# FlightComputer_RevA.net
KiCad netlist of a schematic drawn in EAGLE
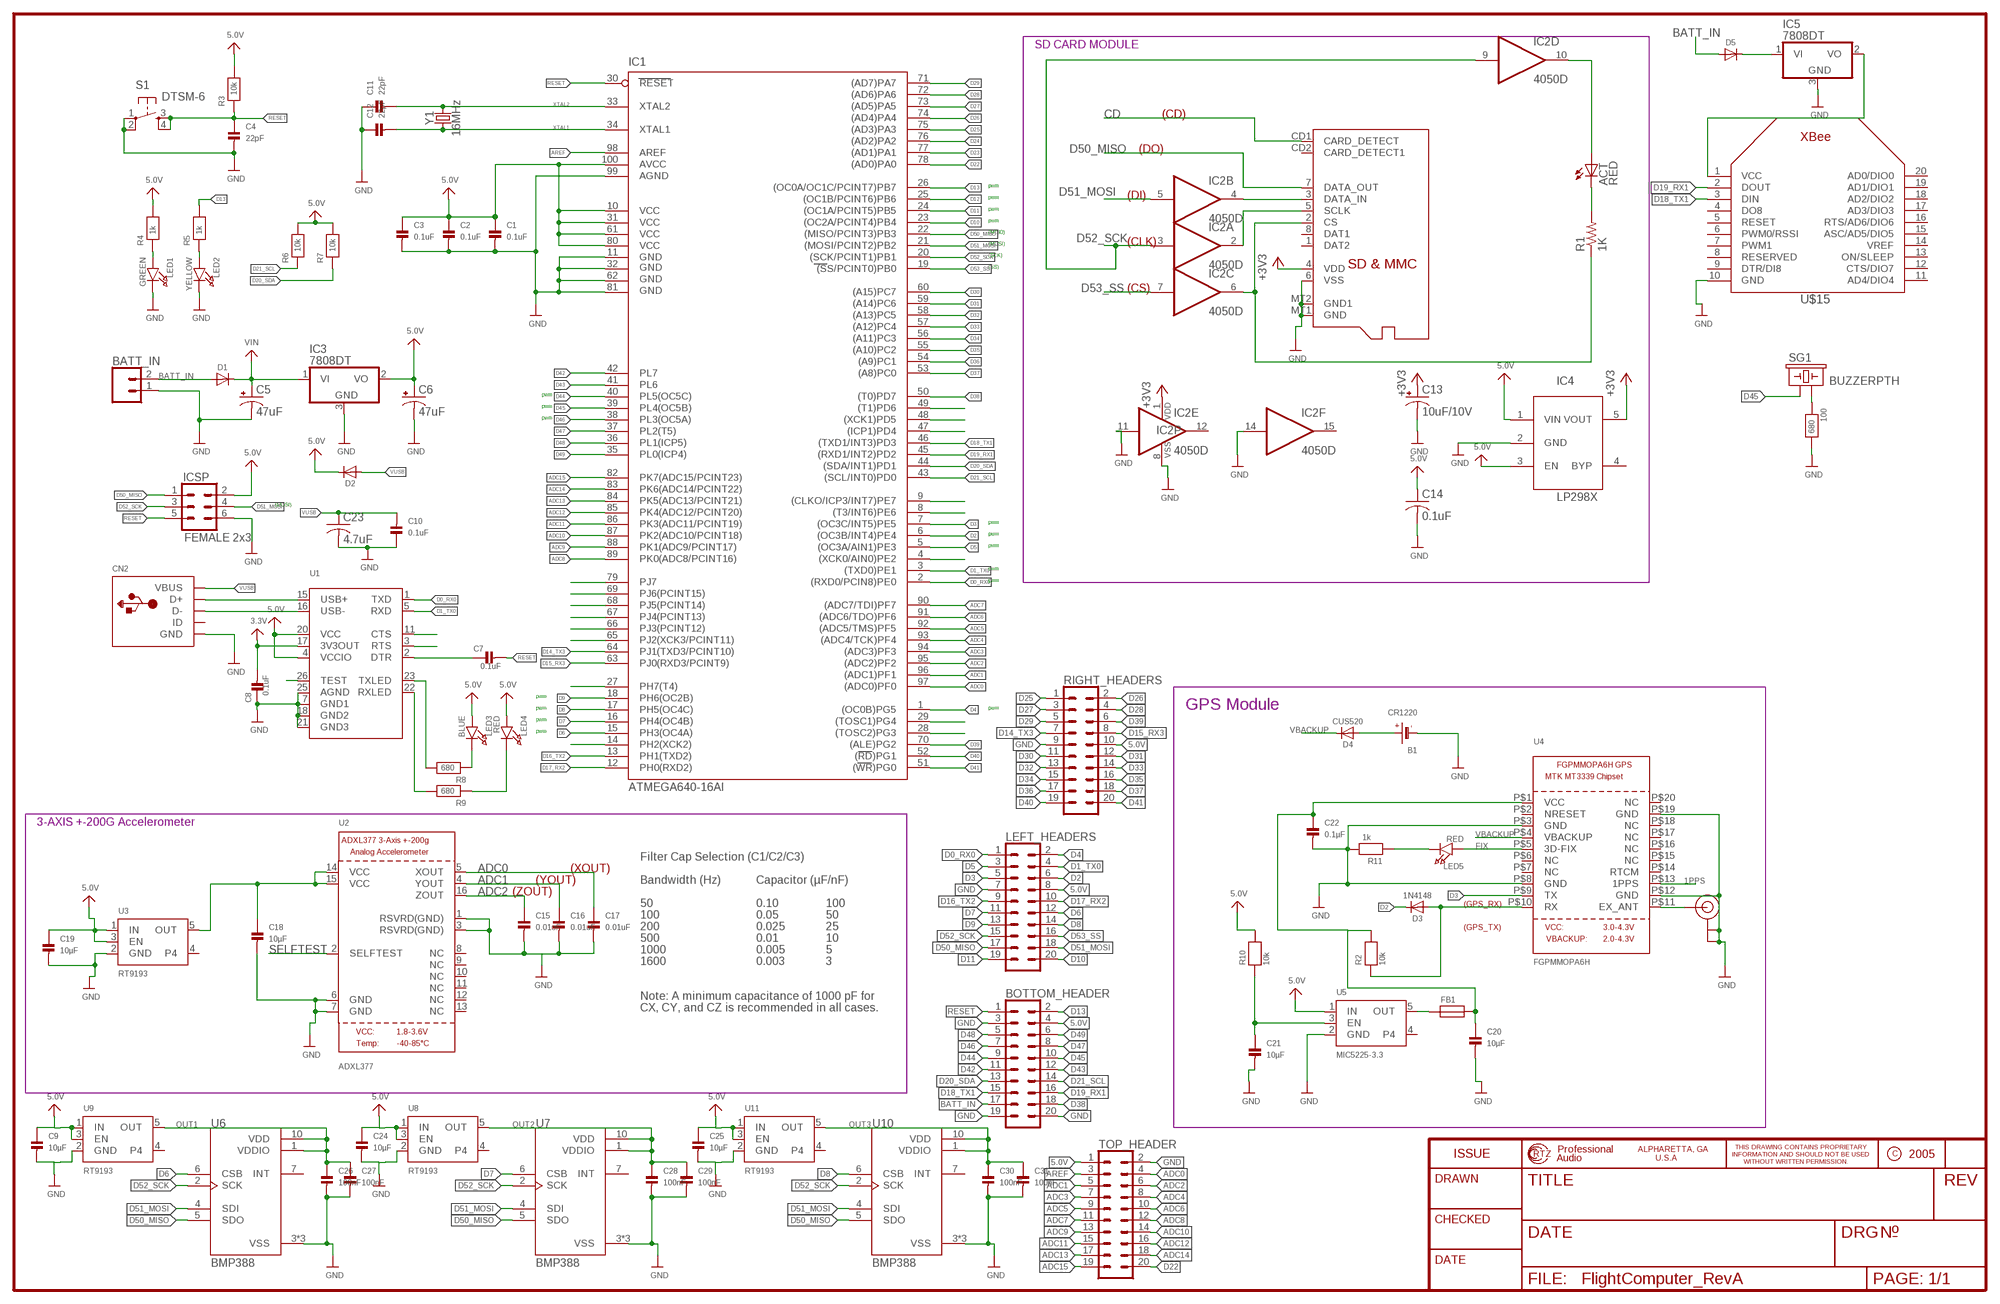
[diagram p0: schematic, sheet 1]

(export (version "E")
  (design (tool "Eeschema 10.0.6"))
  (components
    (comp (ref "100")
      (value "680")
      (footprint "eagle-import:0603")
      (libsource (lib "eagle-import") (part "RESISTOR0603"))
    )
    (comp (ref "ACT")
      (value "RED")
      (footprint "eagle-import:CHIP-LED0805")
      (libsource (lib "eagle-import") (part "LEDCHIP-LED0805"))
    )
    (comp (ref "B1")
      (value "CR1220")
      (footprint "eagle-import:CR1220")
      (libsource (lib "eagle-import") (part "BATTERYCR1220_SMT"))
    )
    (comp (ref "BATT_IN")
      (value "CONN_02")
      (footprint "eagle-import:1X02")
      (libsource (lib "eagle-import") (part "CONN_02"))
    )
    (comp (ref "BOTTOM_HEADER")
      (value "CONN_10X2")
      (footprint "eagle-import:2X10")
      (libsource (lib "eagle-import") (part "CONN_10X2"))
    )
    (comp (ref "C1")
      (value "0.1uF")
      (footprint "eagle-import:0603")
      (libsource (lib "eagle-import") (part "CAP_CERAMIC0603"))
    )
    (comp (ref "C2")
      (value "0.1uF")
      (footprint "eagle-import:0603")
      (libsource (lib "eagle-import") (part "CAP_CERAMIC0603"))
    )
    (comp (ref "C3")
      (value "0.1uF")
      (footprint "eagle-import:0603")
      (libsource (lib "eagle-import") (part "CAP_CERAMIC0603"))
    )
    (comp (ref "C4")
      (value "22pF")
      (footprint "eagle-import:0603")
      (libsource (lib "eagle-import") (part "CAP_CERAMIC0603"))
    )
    (comp (ref "C5")
      (value "47uF")
      (footprint "eagle-import:PANASONIC_D")
      (libsource (lib "eagle-import") (part "rcl_334_CPOL-USD"))
    )
    (comp (ref "C6")
      (value "47uF")
      (footprint "eagle-import:PANASONIC_D")
      (libsource (lib "eagle-import") (part "rcl_334_CPOL-USD"))
    )
    (comp (ref "C7")
      (value "0.1uF")
      (footprint "eagle-import:0603")
      (libsource (lib "eagle-import") (part "CAP_CERAMIC0603"))
    )
    (comp (ref "C8")
      (value "0.1uF")
      (footprint "eagle-import:0603")
      (libsource (lib "eagle-import") (part "CAP_CERAMIC0603"))
    )
    (comp (ref "C9")
      (value "10µF")
      (footprint "eagle-import:0603")
      (libsource (lib "eagle-import") (part "CAP_CERAMIC0603"))
    )
    (comp (ref "C10")
      (value "0.1uF")
      (footprint "eagle-import:0603")
      (libsource (lib "eagle-import") (part "CAP_CERAMIC0603"))
    )
    (comp (ref "C11")
      (value "22pF")
      (footprint "eagle-import:0603")
      (libsource (lib "eagle-import") (part "CAP_CERAMIC0603"))
    )
    (comp (ref "C12")
      (value "22pF")
      (footprint "eagle-import:0603")
      (libsource (lib "eagle-import") (part "CAP_CERAMIC0603"))
    )
    (comp (ref "C13")
      (value "10uF/10V")
      (footprint "eagle-import:A_3216-18R")
      (libsource (lib "eagle-import") (part "CPOL-USA/3216-18R"))
    )
    (comp (ref "C14")
      (value "0.1uF")
      (footprint "eagle-import:C0805K")
      (libsource (lib "eagle-import") (part "C-USC0805K"))
    )
    (comp (ref "C15")
      (value "0.01uF")
      (footprint "eagle-import:0603")
      (libsource (lib "eagle-import") (part "CAP_CERAMIC0603"))
    )
    (comp (ref "C16")
      (value "0.01uF")
      (footprint "eagle-import:0603")
      (libsource (lib "eagle-import") (part "CAP_CERAMIC0603"))
    )
    (comp (ref "C17")
      (value "0.01uF")
      (footprint "eagle-import:0603")
      (libsource (lib "eagle-import") (part "CAP_CERAMIC0603"))
    )
    (comp (ref "C18")
      (value "10µF")
      (footprint "eagle-import:0603")
      (libsource (lib "eagle-import") (part "CAP_CERAMIC0603"))
    )
    (comp (ref "C19")
      (value "10µF")
      (footprint "eagle-import:0603")
      (libsource (lib "eagle-import") (part "CAP_CERAMIC0603"))
    )
    (comp (ref "C20")
      (value "10µF")
      (footprint "eagle-import:0603")
      (libsource (lib "eagle-import") (part "CAP_CERAMIC0603"))
    )
    (comp (ref "C21")
      (value "10µF")
      (footprint "eagle-import:0603")
      (libsource (lib "eagle-import") (part "CAP_CERAMIC0603"))
    )
    (comp (ref "C22")
      (value "0.1µF")
      (footprint "eagle-import:0603")
      (libsource (lib "eagle-import") (part "CAP_CERAMIC0603"))
    )
    (comp (ref "C23")
      (value "4.7uF")
      (footprint "eagle-import:C0603")
      (libsource (lib "eagle-import") (part "C-USC0603"))
    )
    (comp (ref "C24")
      (value "10µF")
      (footprint "eagle-import:0603")
      (libsource (lib "eagle-import") (part "CAP_CERAMIC0603"))
    )
    (comp (ref "C25")
      (value "10µF")
      (footprint "eagle-import:0603")
      (libsource (lib "eagle-import") (part "CAP_CERAMIC0603"))
    )
    (comp (ref "C26")
      (value "100nF")
      (footprint "eagle-import:0603")
      (libsource (lib "eagle-import") (part "CAP_CERAMIC0603"))
    )
    (comp (ref "C27")
      (value "100nF")
      (footprint "eagle-import:0603")
      (libsource (lib "eagle-import") (part "CAP_CERAMIC0603"))
    )
    (comp (ref "C28")
      (value "100nF")
      (footprint "eagle-import:0603")
      (libsource (lib "eagle-import") (part "CAP_CERAMIC0603"))
    )
    (comp (ref "C29")
      (value "100nF")
      (footprint "eagle-import:0603")
      (libsource (lib "eagle-import") (part "CAP_CERAMIC0603"))
    )
    (comp (ref "C30")
      (value "100nF")
      (footprint "eagle-import:0603")
      (libsource (lib "eagle-import") (part "CAP_CERAMIC0603"))
    )
    (comp (ref "C31")
      (value "100nF")
      (footprint "eagle-import:0603")
      (libsource (lib "eagle-import") (part "CAP_CERAMIC0603"))
    )
    (comp (ref "CN2")
      (value "USBMINIB")
      (footprint "eagle-import:USB-MINIB")
      (libsource (lib "eagle-import") (part "USBMINIB"))
    )
    (comp (ref "D1")
      (value "DIODESOD-123")
      (footprint "eagle-import:SOD-123")
      (libsource (lib "eagle-import") (part "DIODESOD-123"))
    )
    (comp (ref "D2")
      (value "DIODESOD-123")
      (footprint "eagle-import:SOD-123")
      (libsource (lib "eagle-import") (part "DIODESOD-123"))
    )
    (comp (ref "D3")
      (value "1N4148")
      (footprint "eagle-import:SOD-323")
      (libsource (lib "eagle-import") (part "DIODESOD-323"))
    )
    (comp (ref "D4")
      (value "CUS520")
      (footprint "eagle-import:SOD-323")
      (libsource (lib "eagle-import") (part "DIODESOD-323"))
    )
    (comp (ref "D5")
      (value "DIODESOD-123")
      (footprint "eagle-import:SOD-123")
      (libsource (lib "eagle-import") (part "DIODESOD-123"))
    )
    (comp (ref "FB1")
      (value "FERRITE")
      (footprint "eagle-import:0603")
      (libsource (lib "eagle-import") (part "FERRITE"))
    )
    (comp (ref "IC1")
      (value "ATMEGA640-16AI")
      (footprint "eagle-import:TQFP100")
      (libsource (lib "eagle-import") (part "ATMEGAAI640-16"))
    )
    (comp (ref "IC2")
      (value "4050D")
      (footprint "eagle-import:SO16")
      (libsource (lib "eagle-import") (part "4050D"))
    )
    (comp (ref "IC3")
      (value "7808DT")
      (footprint "eagle-import:TO252")
      (libsource (lib "eagle-import") (part "78DT08"))
    )
    (comp (ref "IC4")
      (value "LP298XS")
      (footprint "eagle-import:SOT23-5L")
      (libsource (lib "eagle-import") (part "LP298XS"))
    )
    (comp (ref "IC5")
      (value "7808DT")
      (footprint "eagle-import:TO252")
      (libsource (lib "eagle-import") (part "78DT08"))
    )
    (comp (ref "ICSP")
      (value "FEMALE 2x3")
      (footprint "eagle-import:2X3")
      (libsource (lib "eagle-import") (part "CONN_03X2FEMALE"))
    )
    (comp (ref "LED1")
      (value "GREEN")
      (footprint "eagle-import:CHIPLED_0603")
      (libsource (lib "eagle-import") (part "LED0603"))
    )
    (comp (ref "LED2")
      (value "YELLOW")
      (footprint "eagle-import:CHIPLED_0603")
      (libsource (lib "eagle-import") (part "LED0603"))
    )
    (comp (ref "LED3")
      (value "BLUE")
      (footprint "eagle-import:CHIPLED_0603")
      (libsource (lib "eagle-import") (part "LED0603"))
    )
    (comp (ref "LED4")
      (value "RED")
      (footprint "eagle-import:CHIPLED_0603")
      (libsource (lib "eagle-import") (part "LED0603"))
    )
    (comp (ref "LED5")
      (value "RED")
      (footprint "eagle-import:CHIPLED_0805")
      (libsource (lib "eagle-import") (part "LED0805"))
    )
    (comp (ref "LEFT_HEADERS")
      (value "CONN_10X2")
      (footprint "eagle-import:2X10")
      (libsource (lib "eagle-import") (part "CONN_10X2"))
    )
    (comp (ref "R1")
      (value "1K")
      (footprint "eagle-import:R0805")
      (libsource (lib "eagle-import") (part "R-US_R0805"))
    )
    (comp (ref "R2")
      (value "10k")
      (footprint "eagle-import:0603")
      (libsource (lib "eagle-import") (part "RESISTOR0603"))
    )
    (comp (ref "R3")
      (value "10k")
      (footprint "eagle-import:0603")
      (libsource (lib "eagle-import") (part "RESISTOR0603"))
    )
    (comp (ref "R4")
      (value "1k")
      (footprint "eagle-import:0603")
      (libsource (lib "eagle-import") (part "RESISTOR0603"))
    )
    (comp (ref "R5")
      (value "1k")
      (footprint "eagle-import:0603")
      (libsource (lib "eagle-import") (part "RESISTOR0603"))
    )
    (comp (ref "R6")
      (value "10k")
      (footprint "eagle-import:0603")
      (libsource (lib "eagle-import") (part "RESISTOR0603"))
    )
    (comp (ref "R7")
      (value "10k")
      (footprint "eagle-import:0603")
      (libsource (lib "eagle-import") (part "RESISTOR0603"))
    )
    (comp (ref "R8")
      (value "680")
      (footprint "eagle-import:0603")
      (libsource (lib "eagle-import") (part "RESISTOR0603"))
    )
    (comp (ref "R9")
      (value "680")
      (footprint "eagle-import:0603")
      (libsource (lib "eagle-import") (part "RESISTOR0603"))
    )
    (comp (ref "R10")
      (value "10k")
      (footprint "eagle-import:0603")
      (libsource (lib "eagle-import") (part "RESISTOR0603"))
    )
    (comp (ref "R11")
      (value "1k")
      (footprint "eagle-import:0603")
      (libsource (lib "eagle-import") (part "RESISTOR0603"))
    )
    (comp (ref "RIGHT_HEADERS")
      (value "CONN_10X2")
      (footprint "eagle-import:2X10")
      (libsource (lib "eagle-import") (part "CONN_10X2"))
    )
    (comp (ref "S1")
      (value "DTSM-6")
      (footprint "eagle-import:DTSM-6")
      (libsource (lib "eagle-import") (part "DTSM-6"))
    )
    (comp (ref "SG1")
      (value "BUZZERPTH")
      (footprint "eagle-import:BUZZER-12MM")
      (libsource (lib "eagle-import") (part "BUZZERPTH"))
    )
    (comp (ref "TOP_HEADER")
      (value "CONN_10X2")
      (footprint "eagle-import:2X10")
      (libsource (lib "eagle-import") (part "CONN_10X2"))
    )
    (comp (ref "U$15")
      (value "XBEE")
      (footprint "eagle-import:XBEE")
      (libsource (lib "eagle-import") (part "XBEE"))
    )
    (comp (ref "U$55")
      (value "U.FL")
      (footprint "eagle-import:U.FL")
      (libsource (lib "eagle-import") (part "U.FL"))
    )
    (comp (ref "U1")
      (value "FT232RLSSOP28")
      (footprint "eagle-import:SSOP28DB")
      (libsource (lib "eagle-import") (part "FT232RLSSOP28"))
    )
    (comp (ref "U2")
      (value "ADXL377")
      (footprint "eagle-import:LFCSP16_LQ")
      (libsource (lib "eagle-import") (part "ACCEL_ADXL377"))
    )
    (comp (ref "U3")
      (value "RT9193")
      (footprint "eagle-import:SOT23-5")
      (libsource (lib "eagle-import") (part "VREG_SOT23-5"))
    )
    (comp (ref "U4")
      (value "FGPMMOPA6H")
      (footprint "eagle-import:FGPMMOPA6H")
      (libsource (lib "eagle-import") (part "GPS_FGPMMOPA6H"))
    )
    (comp (ref "U5")
      (value "MIC5225-3.3")
      (footprint "eagle-import:SOT23-5")
      (libsource (lib "eagle-import") (part "VREG_SOT23-5"))
    )
    (comp (ref "U6")
      (value "BMP388")
      (footprint "eagle-import:PQFN50P200X200X80-10N")
      (fields (field (name "MF") "Bosch Sensortec"))
      (libsource (lib "eagle-import") (part "BMP388"))
    )
    (comp (ref "U7")
      (value "BMP388")
      (footprint "eagle-import:PQFN50P200X200X80-10N")
      (fields (field (name "MF") "Bosch Sensortec"))
      (libsource (lib "eagle-import") (part "BMP388"))
    )
    (comp (ref "U8")
      (value "RT9193")
      (footprint "eagle-import:SOT23-5")
      (libsource (lib "eagle-import") (part "VREG_SOT23-5"))
    )
    (comp (ref "U9")
      (value "RT9193")
      (footprint "eagle-import:SOT23-5")
      (libsource (lib "eagle-import") (part "VREG_SOT23-5"))
    )
    (comp (ref "U10")
      (value "BMP388")
      (footprint "eagle-import:PQFN50P200X200X80-10N")
      (fields (field (name "MF") "Bosch Sensortec"))
      (libsource (lib "eagle-import") (part "BMP388"))
    )
    (comp (ref "U11")
      (value "RT9193")
      (footprint "eagle-import:SOT23-5")
      (libsource (lib "eagle-import") (part "VREG_SOT23-5"))
    )
    (comp (ref "X1")
      (value "MICROSD")
      (footprint "eagle-import:MICROSD")
      (libsource (lib "eagle-import") (part "MICROSD"))
    )
    (comp (ref "Y1")
      (value "16MHz")
      (footprint "eagle-import:HC49US")
      (libsource (lib "eagle-import") (part "CRYSTAL-16MHZPTH-HC49US"))
    )
  )
  (nets
    (net (code "1") (name "+3V3") (class "Default")
      (node (ref "C13") (pin "+") (pinfunction "+_+") (pintype "passive"))
      (node (ref "IC2") (pin "1") (pinfunction "VDD_1") (pintype "power_in"))
      (node (ref "IC4") (pin "5") (pinfunction "VOUT_5") (pintype "bidirectional"))
      (node (ref "X1") (pin "4") (pinfunction "VDD_4") (pintype "power_in"))
    )
    (net (code "2") (name "/1PPS") (class "Default")
      (node (ref "U4") (pin "P$13") (pinfunction "1PPS_P$13") (pintype "bidirectional"))
    )
    (net (code "3") (name "/CD") (class "Default")
      (node (ref "X1") (pin "CD1") (pinfunction "CARD_DETECT_CD1") (pintype "passive"))
    )
    (net (code "4") (name "/FIX") (class "Default")
      (node (ref "LED5") (pin "A") (pinfunction "A_A") (pintype "passive"))
      (node (ref "U4") (pin "P$5") (pinfunction "3D-FIX_P$5") (pintype "bidirectional"))
    )
    (net (code "5") (name "/OUT1") (class "Default")
      (node (ref "C26") (pin "1") (pinfunction "P$1_1") (pintype "passive"))
      (node (ref "C27") (pin "1") (pinfunction "P$1_1") (pintype "passive"))
      (node (ref "U6") (pin "1") (pinfunction "VDDIO_1") (pintype "power_in"))
      (node (ref "U6") (pin "10") (pinfunction "VDD_10") (pintype "power_in"))
      (node (ref "U9") (pin "5") (pinfunction "OUT_5") (pintype "power_in"))
    )
    (net (code "6") (name "/OUT2") (class "Default")
      (node (ref "C28") (pin "1") (pinfunction "P$1_1") (pintype "passive"))
      (node (ref "C29") (pin "1") (pinfunction "P$1_1") (pintype "passive"))
      (node (ref "U7") (pin "1") (pinfunction "VDDIO_1") (pintype "power_in"))
      (node (ref "U7") (pin "10") (pinfunction "VDD_10") (pintype "power_in"))
      (node (ref "U8") (pin "5") (pinfunction "OUT_5") (pintype "power_in"))
    )
    (net (code "7") (name "/OUT3") (class "Default")
      (node (ref "C30") (pin "1") (pinfunction "P$1_1") (pintype "passive"))
      (node (ref "C31") (pin "1") (pinfunction "P$1_1") (pintype "passive"))
      (node (ref "U10") (pin "1") (pinfunction "VDDIO_1") (pintype "power_in"))
      (node (ref "U10") (pin "10") (pinfunction "VDD_10") (pintype "power_in"))
      (node (ref "U11") (pin "5") (pinfunction "OUT_5") (pintype "power_in"))
    )
    (net (code "8") (name "/SELFTEST") (class "Default")
      (node (ref "U2") (pin "2") (pinfunction "SELFTEST_2") (pintype "bidirectional"))
    )
    (net (code "9") (name "/VBACKUP") (class "Default")
      (node (ref "D4") (pin "C") (pinfunction "C_C") (pintype "passive"))
      (node (ref "U4") (pin "P$4") (pinfunction "VBACKUP_P$4") (pintype "bidirectional"))
    )
    (net (code "10") (name "/XTAL1") (class "Default")
      (node (ref "C12") (pin "2") (pinfunction "P$2_2") (pintype "passive"))
      (node (ref "IC1") (pin "34") (pinfunction "XTAL1_34") (pintype "input"))
      (node (ref "Y1") (pin "1") (pinfunction "1_1") (pintype "passive"))
    )
    (net (code "11") (name "/XTAL2") (class "Default")
      (node (ref "C11") (pin "2") (pinfunction "P$2_2") (pintype "passive"))
      (node (ref "IC1") (pin "33") (pinfunction "XTAL2_33") (pintype "output"))
      (node (ref "Y1") (pin "2") (pinfunction "2_2") (pintype "passive"))
    )
    (net (code "12") (name "3.3V") (class "Default")
      (node (ref "C8") (pin "2") (pinfunction "P$2_2") (pintype "passive"))
      (node (ref "U1") (pin "17") (pinfunction "3V3OUT_17") (pintype "power_in"))
    )
    (net (code "13") (name "5.0V") (class "Default")
      (node (ref "BOTTOM_HEADER") (pin "4") (pinfunction "4_4") (pintype "passive"))
      (node (ref "C1") (pin "1") (pinfunction "P$1_1") (pintype "passive"))
      (node (ref "C14") (pin "1") (pinfunction "1_1") (pintype "passive"))
      (node (ref "C19") (pin "1") (pinfunction "P$1_1") (pintype "passive"))
      (node (ref "C2") (pin "1") (pinfunction "P$1_1") (pintype "passive"))
      (node (ref "C24") (pin "1") (pinfunction "P$1_1") (pintype "passive"))
      (node (ref "C25") (pin "1") (pinfunction "P$1_1") (pintype "passive"))
      (node (ref "C3") (pin "1") (pinfunction "P$1_1") (pintype "passive"))
      (node (ref "C6") (pin "+") (pinfunction "+_+") (pintype "passive"))
      (node (ref "C9") (pin "1") (pinfunction "P$1_1") (pintype "passive"))
      (node (ref "D2") (pin "C") (pinfunction "C_C") (pintype "passive"))
      (node (ref "IC1") (pin "10") (pinfunction "VCC_10") (pintype "power_in"))
      (node (ref "IC1") (pin "100") (pinfunction "AVCC_100") (pintype "power_in"))
      (node (ref "IC1") (pin "31") (pinfunction "VCC1_31") (pintype "power_in"))
      (node (ref "IC1") (pin "61") (pinfunction "VCC2_61") (pintype "power_in"))
      (node (ref "IC1") (pin "80") (pinfunction "VCC3_80") (pintype "power_in"))
      (node (ref "IC3") (pin "2") (pinfunction "VO_2") (pintype "passive"))
      (node (ref "IC4") (pin "1") (pinfunction "VIN_1") (pintype "bidirectional"))
      (node (ref "IC4") (pin "3") (pinfunction "EN_3") (pintype "bidirectional"))
      (node (ref "ICSP") (pin "2") (pinfunction "2_2") (pintype "bidirectional"))
      (node (ref "LED3") (pin "A") (pinfunction "A_A") (pintype "passive"))
      (node (ref "LED4") (pin "A") (pinfunction "A_A") (pintype "passive"))
      (node (ref "LEFT_HEADERS") (pin "8") (pinfunction "8_8") (pintype "passive"))
      (node (ref "R10") (pin "2") (pinfunction "2_2") (pintype "passive"))
      (node (ref "R3") (pin "2") (pinfunction "2_2") (pintype "passive"))
      (node (ref "R4") (pin "2") (pinfunction "2_2") (pintype "passive"))
      (node (ref "R6") (pin "2") (pinfunction "2_2") (pintype "passive"))
      (node (ref "R7") (pin "2") (pinfunction "2_2") (pintype "passive"))
      (node (ref "RIGHT_HEADERS") (pin "10") (pinfunction "10_10") (pintype "passive"))
      (node (ref "TOP_HEADER") (pin "1") (pinfunction "1_1") (pintype "passive"))
      (node (ref "U1") (pin "20") (pinfunction "VCC_20") (pintype "power_in"))
      (node (ref "U1") (pin "4") (pinfunction "VCCIO_4") (pintype "power_in"))
      (node (ref "U11") (pin "1") (pinfunction "IN_1") (pintype "power_in"))
      (node (ref "U11") (pin "3") (pinfunction "EN_3") (pintype "input"))
      (node (ref "U3") (pin "1") (pinfunction "IN_1") (pintype "power_in"))
      (node (ref "U3") (pin "3") (pinfunction "EN_3") (pintype "input"))
      (node (ref "U5") (pin "1") (pinfunction "IN_1") (pintype "power_in"))
      (node (ref "U8") (pin "1") (pinfunction "IN_1") (pintype "power_in"))
      (node (ref "U8") (pin "3") (pinfunction "EN_3") (pintype "input"))
      (node (ref "U9") (pin "1") (pinfunction "IN_1") (pintype "power_in"))
      (node (ref "U9") (pin "3") (pinfunction "EN_3") (pintype "input"))
    )
    (net (code "14") (name "ADC0") (class "Default")
      (node (ref "C17") (pin "1") (pinfunction "P$1_1") (pintype "passive"))
      (node (ref "IC1") (pin "97") (pinfunction "(ADC0)PF0_97") (pintype "bidirectional"))
      (node (ref "TOP_HEADER") (pin "4") (pinfunction "4_4") (pintype "passive"))
      (node (ref "U2") (pin "5") (pinfunction "XOUT_5") (pintype "output"))
    )
    (net (code "15") (name "ADC1") (class "Default")
      (node (ref "C16") (pin "1") (pinfunction "P$1_1") (pintype "passive"))
      (node (ref "IC1") (pin "96") (pinfunction "(ADC1)PF1_96") (pintype "bidirectional"))
      (node (ref "TOP_HEADER") (pin "5") (pinfunction "5_5") (pintype "passive"))
      (node (ref "U2") (pin "4") (pinfunction "YOUT_4") (pintype "output"))
    )
    (net (code "16") (name "ADC2") (class "Default")
      (node (ref "C15") (pin "1") (pinfunction "P$1_1") (pintype "passive"))
      (node (ref "IC1") (pin "95") (pinfunction "(ADC2)PF2_95") (pintype "bidirectional"))
      (node (ref "TOP_HEADER") (pin "6") (pinfunction "6_6") (pintype "passive"))
      (node (ref "U2") (pin "16") (pinfunction "ZOUT_16") (pintype "output"))
    )
    (net (code "17") (name "ADC3") (class "Default")
      (node (ref "IC1") (pin "94") (pinfunction "(ADC3)PF3_94") (pintype "bidirectional"))
      (node (ref "TOP_HEADER") (pin "7") (pinfunction "7_7") (pintype "passive"))
    )
    (net (code "18") (name "ADC4") (class "Default")
      (node (ref "IC1") (pin "93") (pinfunction "(ADC4/TCK)PF4_93") (pintype "bidirectional"))
      (node (ref "TOP_HEADER") (pin "8") (pinfunction "8_8") (pintype "passive"))
    )
    (net (code "19") (name "ADC5") (class "Default")
      (node (ref "IC1") (pin "92") (pinfunction "(ADC5/TMS)PF5_92") (pintype "bidirectional"))
      (node (ref "TOP_HEADER") (pin "9") (pinfunction "9_9") (pintype "passive"))
    )
    (net (code "20") (name "ADC6") (class "Default")
      (node (ref "IC1") (pin "91") (pinfunction "(ADC6/TDO)PF6_91") (pintype "bidirectional"))
      (node (ref "TOP_HEADER") (pin "10") (pinfunction "10_10") (pintype "passive"))
    )
    (net (code "21") (name "ADC7") (class "Default")
      (node (ref "IC1") (pin "90") (pinfunction "(ADC7/TDI)PF7_90") (pintype "bidirectional"))
      (node (ref "TOP_HEADER") (pin "11") (pinfunction "11_11") (pintype "passive"))
    )
    (net (code "22") (name "ADC8") (class "Default")
      (node (ref "IC1") (pin "89") (pinfunction "PK0(ADC8/PCINT16)_89") (pintype "bidirectional"))
      (node (ref "TOP_HEADER") (pin "12") (pinfunction "12_12") (pintype "passive"))
    )
    (net (code "23") (name "ADC9") (class "Default")
      (node (ref "IC1") (pin "88") (pinfunction "PK1(ADC9/PCINT17)_88") (pintype "bidirectional"))
      (node (ref "TOP_HEADER") (pin "13") (pinfunction "13_13") (pintype "passive"))
    )
    (net (code "24") (name "ADC10") (class "Default")
      (node (ref "IC1") (pin "87") (pinfunction "PK2(ADC10/PCINT18)_87") (pintype "bidirectional"))
      (node (ref "TOP_HEADER") (pin "14") (pinfunction "14_14") (pintype "passive"))
    )
    (net (code "25") (name "ADC11") (class "Default")
      (node (ref "IC1") (pin "86") (pinfunction "PK3(ADC11/PCINT19)_86") (pintype "bidirectional"))
      (node (ref "TOP_HEADER") (pin "15") (pinfunction "15_15") (pintype "passive"))
    )
    (net (code "26") (name "ADC12") (class "Default")
      (node (ref "IC1") (pin "85") (pinfunction "PK4(ADC12/PCINT20)_85") (pintype "bidirectional"))
      (node (ref "TOP_HEADER") (pin "16") (pinfunction "16_16") (pintype "passive"))
    )
    (net (code "27") (name "ADC13") (class "Default")
      (node (ref "IC1") (pin "84") (pinfunction "PK5(ADC13/PCINT21)_84") (pintype "bidirectional"))
      (node (ref "TOP_HEADER") (pin "17") (pinfunction "17_17") (pintype "passive"))
    )
    (net (code "28") (name "ADC14") (class "Default")
      (node (ref "IC1") (pin "83") (pinfunction "PK6(ADC14/PCINT22)_83") (pintype "bidirectional"))
      (node (ref "TOP_HEADER") (pin "18") (pinfunction "18_18") (pintype "passive"))
    )
    (net (code "29") (name "ADC15") (class "Default")
      (node (ref "IC1") (pin "82") (pinfunction "PK7(ADC15/PCINT23)_82") (pintype "bidirectional"))
      (node (ref "TOP_HEADER") (pin "19") (pinfunction "19_19") (pintype "passive"))
    )
    (net (code "30") (name "AREF") (class "Default")
      (node (ref "IC1") (pin "98") (pinfunction "AREF_98") (pintype "bidirectional"))
      (node (ref "TOP_HEADER") (pin "3") (pinfunction "3_3") (pintype "passive"))
    )
    (net (code "31") (name "BATT_IN") (class "Default")
      (node (ref "BATT_IN") (pin "2") (pinfunction "2_2") (pintype "passive"))
      (node (ref "BOTTOM_HEADER") (pin "17") (pinfunction "17_17") (pintype "passive"))
      (node (ref "D1") (pin "A") (pinfunction "A_A") (pintype "passive"))
      (node (ref "D5") (pin "A") (pinfunction "A_A") (pintype "passive"))
    )
    (net (code "32") (name "D0_RX0") (class "Default")
      (node (ref "IC1") (pin "2") (pinfunction "(RXD0/PCIN8)PE0_2") (pintype "bidirectional"))
      (node (ref "LEFT_HEADERS") (pin "1") (pinfunction "1_1") (pintype "passive"))
      (node (ref "U1") (pin "1") (pinfunction "TXD_1") (pintype "output"))
    )
    (net (code "33") (name "D1_TX0") (class "Default")
      (node (ref "IC1") (pin "3") (pinfunction "(TXD0)PE1_3") (pintype "bidirectional"))
      (node (ref "LEFT_HEADERS") (pin "4") (pinfunction "4_4") (pintype "passive"))
      (node (ref "U1") (pin "5") (pinfunction "RXD_5") (pintype "input"))
    )
    (net (code "34") (name "D2") (class "Default")
      (node (ref "D3") (pin "C") (pinfunction "C_C") (pintype "passive"))
      (node (ref "IC1") (pin "6") (pinfunction "(OC3B/INT4)PE4_6") (pintype "bidirectional"))
      (node (ref "LEFT_HEADERS") (pin "6") (pinfunction "6_6") (pintype "passive"))
    )
    (net (code "35") (name "D3") (class "Default")
      (node (ref "IC1") (pin "7") (pinfunction "(OC3C/INT5)PE5_7") (pintype "bidirectional"))
      (node (ref "LEFT_HEADERS") (pin "5") (pinfunction "5_5") (pintype "passive"))
      (node (ref "U4") (pin "P$9") (pinfunction "TX_P$9") (pintype "bidirectional"))
    )
    (net (code "36") (name "D4") (class "Default")
      (node (ref "IC1") (pin "1") (pinfunction "(OC0B)PG5_1") (pintype "bidirectional"))
      (node (ref "LEFT_HEADERS") (pin "2") (pinfunction "2_2") (pintype "passive"))
    )
    (net (code "37") (name "D5") (class "Default")
      (node (ref "IC1") (pin "5") (pinfunction "(OC3A/AIN1)PE3_5") (pintype "bidirectional"))
      (node (ref "LEFT_HEADERS") (pin "3") (pinfunction "3_3") (pintype "passive"))
    )
    (net (code "38") (name "D6") (class "Default")
      (node (ref "IC1") (pin "15") (pinfunction "PH3(OC4A)_15") (pintype "bidirectional"))
      (node (ref "LEFT_HEADERS") (pin "12") (pinfunction "12_12") (pintype "passive"))
      (node (ref "U6") (pin "6") (pinfunction "CSB_6") (pintype "input"))
    )
    (net (code "39") (name "D7") (class "Default")
      (node (ref "IC1") (pin "16") (pinfunction "PH4(OC4B)_16") (pintype "bidirectional"))
      (node (ref "LEFT_HEADERS") (pin "11") (pinfunction "11_11") (pintype "passive"))
      (node (ref "U7") (pin "6") (pinfunction "CSB_6") (pintype "input"))
    )
    (net (code "40") (name "D8") (class "Default")
      (node (ref "IC1") (pin "17") (pinfunction "PH5(OC4C)_17") (pintype "bidirectional"))
      (node (ref "LEFT_HEADERS") (pin "14") (pinfunction "14_14") (pintype "passive"))
      (node (ref "U10") (pin "6") (pinfunction "CSB_6") (pintype "input"))
    )
    (net (code "41") (name "D9") (class "Default")
      (node (ref "IC1") (pin "18") (pinfunction "PH6(OC2B)_18") (pintype "bidirectional"))
      (node (ref "LEFT_HEADERS") (pin "13") (pinfunction "13_13") (pintype "passive"))
    )
    (net (code "42") (name "D10") (class "Default")
      (node (ref "IC1") (pin "23") (pinfunction "(OC2A/PCINT4)PB4_23") (pintype "bidirectional"))
      (node (ref "LEFT_HEADERS") (pin "20") (pinfunction "20_20") (pintype "passive"))
    )
    (net (code "43") (name "D11") (class "Default")
      (node (ref "IC1") (pin "24") (pinfunction "(OC1A/PCINT5)PB5_24") (pintype "bidirectional"))
      (node (ref "LEFT_HEADERS") (pin "19") (pinfunction "19_19") (pintype "passive"))
    )
    (net (code "44") (name "D12") (class "Default")
      (node (ref "IC1") (pin "25") (pinfunction "(OC1B/PCINT6)PB6_25") (pintype "bidirectional"))
    )
    (net (code "45") (name "D13") (class "Default")
      (node (ref "BOTTOM_HEADER") (pin "2") (pinfunction "2_2") (pintype "passive"))
      (node (ref "IC1") (pin "26") (pinfunction "(OC0A/OC1C/PCINT7)PB7_26") (pintype "bidirectional"))
      (node (ref "R5") (pin "2") (pinfunction "2_2") (pintype "passive"))
    )
    (net (code "46") (name "D14_TX3") (class "Default")
      (node (ref "IC1") (pin "64") (pinfunction "PJ1(TXD3/PCINT10)_64") (pintype "bidirectional"))
      (node (ref "RIGHT_HEADERS") (pin "7") (pinfunction "7_7") (pintype "passive"))
    )
    (net (code "47") (name "D15_RX3") (class "Default")
      (node (ref "IC1") (pin "63") (pinfunction "PJ0(RXD3/PCINT9)_63") (pintype "bidirectional"))
      (node (ref "RIGHT_HEADERS") (pin "8") (pinfunction "8_8") (pintype "passive"))
    )
    (net (code "48") (name "D16_TX2") (class "Default")
      (node (ref "IC1") (pin "13") (pinfunction "PH1(TXD2)_13") (pintype "bidirectional"))
      (node (ref "LEFT_HEADERS") (pin "9") (pinfunction "9_9") (pintype "passive"))
    )
    (net (code "49") (name "D17_RX2") (class "Default")
      (node (ref "IC1") (pin "12") (pinfunction "PH0(RXD2)_12") (pintype "bidirectional"))
      (node (ref "LEFT_HEADERS") (pin "10") (pinfunction "10_10") (pintype "passive"))
    )
    (net (code "50") (name "D18_TX1") (class "Default")
      (node (ref "BOTTOM_HEADER") (pin "15") (pinfunction "15_15") (pintype "passive"))
      (node (ref "IC1") (pin "46") (pinfunction "(TXD1/INT3)PD3_46") (pintype "bidirectional"))
      (node (ref "U$15") (pin "3") (pinfunction "DIN_3") (pintype "input"))
    )
    (net (code "51") (name "D19_RX1") (class "Default")
      (node (ref "BOTTOM_HEADER") (pin "16") (pinfunction "16_16") (pintype "passive"))
      (node (ref "IC1") (pin "45") (pinfunction "(RXD1/INT2)PD2_45") (pintype "bidirectional"))
      (node (ref "U$15") (pin "2") (pinfunction "DOUT_2") (pintype "output"))
    )
    (net (code "52") (name "D20_SDA") (class "Default")
      (node (ref "BOTTOM_HEADER") (pin "13") (pinfunction "13_13") (pintype "passive"))
      (node (ref "IC1") (pin "44") (pinfunction "(SDA/INT1)PD1_44") (pintype "bidirectional"))
      (node (ref "R7") (pin "1") (pinfunction "1_1") (pintype "passive"))
    )
    (net (code "53") (name "D21_SCL") (class "Default")
      (node (ref "BOTTOM_HEADER") (pin "14") (pinfunction "14_14") (pintype "passive"))
      (node (ref "IC1") (pin "43") (pinfunction "(SCL/INT0)PD0_43") (pintype "bidirectional"))
      (node (ref "R6") (pin "1") (pinfunction "1_1") (pintype "passive"))
    )
    (net (code "54") (name "D22") (class "Default")
      (node (ref "IC1") (pin "78") (pinfunction "(AD0)PA0_78") (pintype "bidirectional"))
      (node (ref "TOP_HEADER") (pin "20") (pinfunction "20_20") (pintype "passive"))
    )
    (net (code "55") (name "D23") (class "Default")
      (node (ref "IC1") (pin "77") (pinfunction "(AD1)PA1_77") (pintype "bidirectional"))
    )
    (net (code "56") (name "D24") (class "Default")
      (node (ref "IC1") (pin "76") (pinfunction "(AD2)PA2_76") (pintype "bidirectional"))
    )
    (net (code "57") (name "D25") (class "Default")
      (node (ref "IC1") (pin "75") (pinfunction "(AD3)PA3_75") (pintype "bidirectional"))
      (node (ref "RIGHT_HEADERS") (pin "1") (pinfunction "1_1") (pintype "passive"))
    )
    (net (code "58") (name "D26") (class "Default")
      (node (ref "IC1") (pin "74") (pinfunction "(AD4)PA4_74") (pintype "bidirectional"))
      (node (ref "RIGHT_HEADERS") (pin "2") (pinfunction "2_2") (pintype "passive"))
    )
    (net (code "59") (name "D27") (class "Default")
      (node (ref "IC1") (pin "73") (pinfunction "(AD5)PA5_73") (pintype "bidirectional"))
      (node (ref "RIGHT_HEADERS") (pin "3") (pinfunction "3_3") (pintype "passive"))
    )
    (net (code "60") (name "D28") (class "Default")
      (node (ref "IC1") (pin "72") (pinfunction "(AD6)PA6_72") (pintype "bidirectional"))
      (node (ref "RIGHT_HEADERS") (pin "4") (pinfunction "4_4") (pintype "passive"))
    )
    (net (code "61") (name "D29") (class "Default")
      (node (ref "IC1") (pin "71") (pinfunction "(AD7)PA7_71") (pintype "bidirectional"))
      (node (ref "RIGHT_HEADERS") (pin "5") (pinfunction "5_5") (pintype "passive"))
    )
    (net (code "62") (name "D30") (class "Default")
      (node (ref "IC1") (pin "60") (pinfunction "(A15)PC7_60") (pintype "bidirectional"))
      (node (ref "RIGHT_HEADERS") (pin "11") (pinfunction "11_11") (pintype "passive"))
    )
    (net (code "63") (name "D31") (class "Default")
      (node (ref "IC1") (pin "59") (pinfunction "(A14)PC6_59") (pintype "bidirectional"))
      (node (ref "RIGHT_HEADERS") (pin "12") (pinfunction "12_12") (pintype "passive"))
    )
    (net (code "64") (name "D32") (class "Default")
      (node (ref "IC1") (pin "58") (pinfunction "(A13)PC5_58") (pintype "bidirectional"))
      (node (ref "RIGHT_HEADERS") (pin "13") (pinfunction "13_13") (pintype "passive"))
    )
    (net (code "65") (name "D33") (class "Default")
      (node (ref "IC1") (pin "57") (pinfunction "(A12)PC4_57") (pintype "bidirectional"))
      (node (ref "RIGHT_HEADERS") (pin "14") (pinfunction "14_14") (pintype "passive"))
    )
    (net (code "66") (name "D34") (class "Default")
      (node (ref "IC1") (pin "56") (pinfunction "(A11)PC3_56") (pintype "bidirectional"))
      (node (ref "RIGHT_HEADERS") (pin "15") (pinfunction "15_15") (pintype "passive"))
    )
    (net (code "67") (name "D35") (class "Default")
      (node (ref "IC1") (pin "55") (pinfunction "(A10)PC2_55") (pintype "bidirectional"))
      (node (ref "RIGHT_HEADERS") (pin "16") (pinfunction "16_16") (pintype "passive"))
    )
    (net (code "68") (name "D36") (class "Default")
      (node (ref "IC1") (pin "54") (pinfunction "(A9)PC1_54") (pintype "bidirectional"))
      (node (ref "RIGHT_HEADERS") (pin "17") (pinfunction "17_17") (pintype "passive"))
    )
    (net (code "69") (name "D37") (class "Default")
      (node (ref "IC1") (pin "53") (pinfunction "(A8)PC0_53") (pintype "bidirectional"))
      (node (ref "RIGHT_HEADERS") (pin "18") (pinfunction "18_18") (pintype "passive"))
    )
    (net (code "70") (name "D38") (class "Default")
      (node (ref "BOTTOM_HEADER") (pin "18") (pinfunction "18_18") (pintype "passive"))
      (node (ref "IC1") (pin "50") (pinfunction "(T0)PD7_50") (pintype "bidirectional"))
    )
    (net (code "71") (name "D39") (class "Default")
      (node (ref "IC1") (pin "70") (pinfunction "(ALE)PG2_70") (pintype "bidirectional"))
      (node (ref "RIGHT_HEADERS") (pin "6") (pinfunction "6_6") (pintype "passive"))
    )
    (net (code "72") (name "D40") (class "Default")
      (node (ref "IC1") (pin "52") (pinfunction "(RD)PG1_52") (pintype "bidirectional"))
      (node (ref "RIGHT_HEADERS") (pin "19") (pinfunction "19_19") (pintype "passive"))
    )
    (net (code "73") (name "D41") (class "Default")
      (node (ref "IC1") (pin "51") (pinfunction "(WR)PG0_51") (pintype "bidirectional"))
      (node (ref "RIGHT_HEADERS") (pin "20") (pinfunction "20_20") (pintype "passive"))
    )
    (net (code "74") (name "D42") (class "Default")
      (node (ref "BOTTOM_HEADER") (pin "11") (pinfunction "11_11") (pintype "passive"))
      (node (ref "IC1") (pin "42") (pinfunction "PL7_42") (pintype "bidirectional"))
    )
    (net (code "75") (name "D43") (class "Default")
      (node (ref "BOTTOM_HEADER") (pin "12") (pinfunction "12_12") (pintype "passive"))
      (node (ref "IC1") (pin "41") (pinfunction "PL6_41") (pintype "bidirectional"))
    )
    (net (code "76") (name "D44") (class "Default")
      (node (ref "BOTTOM_HEADER") (pin "9") (pinfunction "9_9") (pintype "passive"))
      (node (ref "IC1") (pin "40") (pinfunction "PL5(OC5C)_40") (pintype "bidirectional"))
    )
    (net (code "77") (name "D45") (class "Default")
      (node (ref "BOTTOM_HEADER") (pin "10") (pinfunction "10_10") (pintype "passive"))
      (node (ref "IC1") (pin "39") (pinfunction "PL4(OC5B)_39") (pintype "bidirectional"))
      (node (ref "SG1") (pin "+") (pinfunction "1_+") (pintype "passive"))
    )
    (net (code "78") (name "D46") (class "Default")
      (node (ref "BOTTOM_HEADER") (pin "7") (pinfunction "7_7") (pintype "passive"))
      (node (ref "IC1") (pin "38") (pinfunction "PL3(OC5A)_38") (pintype "bidirectional"))
    )
    (net (code "79") (name "D47") (class "Default")
      (node (ref "BOTTOM_HEADER") (pin "8") (pinfunction "8_8") (pintype "passive"))
      (node (ref "IC1") (pin "37") (pinfunction "PL2(T5)_37") (pintype "bidirectional"))
    )
    (net (code "80") (name "D48") (class "Default")
      (node (ref "BOTTOM_HEADER") (pin "5") (pinfunction "5_5") (pintype "passive"))
      (node (ref "IC1") (pin "36") (pinfunction "PL1(ICP5)_36") (pintype "bidirectional"))
    )
    (net (code "81") (name "D49") (class "Default")
      (node (ref "BOTTOM_HEADER") (pin "6") (pinfunction "6_6") (pintype "passive"))
      (node (ref "IC1") (pin "35") (pinfunction "PL0(ICP4)_35") (pintype "bidirectional"))
    )
    (net (code "82") (name "D50_MISO") (class "Default")
      (node (ref "IC1") (pin "22") (pinfunction "(MISO/PCINT3)PB3_22") (pintype "bidirectional"))
      (node (ref "ICSP") (pin "1") (pinfunction "1_1") (pintype "bidirectional"))
      (node (ref "LEFT_HEADERS") (pin "17") (pinfunction "17_17") (pintype "passive"))
      (node (ref "U10") (pin "5") (pinfunction "SDO_5") (pintype "bidirectional"))
      (node (ref "U6") (pin "5") (pinfunction "SDO_5") (pintype "bidirectional"))
      (node (ref "U7") (pin "5") (pinfunction "SDO_5") (pintype "bidirectional"))
      (node (ref "X1") (pin "7") (pinfunction "DATA_OUT_7") (pintype "output"))
    )
    (net (code "83") (name "D51_MOSI") (class "Default")
      (node (ref "IC1") (pin "21") (pinfunction "(MOSI/PCINT2)PB2_21") (pintype "bidirectional"))
      (node (ref "IC2") (pin "5") (pinfunction "I_5") (pintype "input"))
      (node (ref "ICSP") (pin "4") (pinfunction "4_4") (pintype "bidirectional"))
      (node (ref "LEFT_HEADERS") (pin "18") (pinfunction "18_18") (pintype "passive"))
      (node (ref "U10") (pin "4") (pinfunction "SDI_4") (pintype "bidirectional"))
      (node (ref "U6") (pin "4") (pinfunction "SDI_4") (pintype "bidirectional"))
      (node (ref "U7") (pin "4") (pinfunction "SDI_4") (pintype "bidirectional"))
    )
    (net (code "84") (name "D52_SCK") (class "Default")
      (node (ref "IC1") (pin "20") (pinfunction "(SCK/PCINT1)PB1_20") (pintype "bidirectional"))
      (node (ref "IC2") (pin "3") (pinfunction "I_3") (pintype "input"))
      (node (ref "IC2") (pin "9") (pinfunction "I_9") (pintype "input"))
      (node (ref "ICSP") (pin "3") (pinfunction "3_3") (pintype "bidirectional"))
      (node (ref "LEFT_HEADERS") (pin "15") (pinfunction "15_15") (pintype "passive"))
      (node (ref "U10") (pin "2") (pinfunction "SCK_2") (pintype "input"))
      (node (ref "U6") (pin "2") (pinfunction "SCK_2") (pintype "input"))
      (node (ref "U7") (pin "2") (pinfunction "SCK_2") (pintype "input"))
    )
    (net (code "85") (name "D53_SS") (class "Default")
      (node (ref "IC1") (pin "19") (pinfunction "(SS/PCINT0)PB0_19") (pintype "bidirectional"))
      (node (ref "IC2") (pin "7") (pinfunction "I_7") (pintype "input"))
      (node (ref "LEFT_HEADERS") (pin "16") (pinfunction "16_16") (pintype "passive"))
    )
    (net (code "86") (name "GND") (class "Default")
      (node (ref "100") (pin "2") (pinfunction "2_2") (pintype "passive"))
      (node (ref "B1") (pin "-") (pinfunction "-_-") (pintype "passive"))
      (node (ref "BATT_IN") (pin "1") (pinfunction "1_1") (pintype "passive"))
      (node (ref "BOTTOM_HEADER") (pin "19") (pinfunction "19_19") (pintype "passive"))
      (node (ref "BOTTOM_HEADER") (pin "20") (pinfunction "20_20") (pintype "passive"))
      (node (ref "BOTTOM_HEADER") (pin "3") (pinfunction "3_3") (pintype "passive"))
      (node (ref "C1") (pin "2") (pinfunction "P$2_2") (pintype "passive"))
      (node (ref "C10") (pin "1") (pinfunction "P$1_1") (pintype "passive"))
      (node (ref "C11") (pin "1") (pinfunction "P$1_1") (pintype "passive"))
      (node (ref "C12") (pin "1") (pinfunction "P$1_1") (pintype "passive"))
      (node (ref "C13") (pin "-") (pinfunction "-_-") (pintype "passive"))
      (node (ref "C14") (pin "2") (pinfunction "2_2") (pintype "passive"))
      (node (ref "C15") (pin "2") (pinfunction "P$2_2") (pintype "passive"))
      (node (ref "C16") (pin "2") (pinfunction "P$2_2") (pintype "passive"))
      (node (ref "C17") (pin "2") (pinfunction "P$2_2") (pintype "passive"))
      (node (ref "C18") (pin "2") (pinfunction "P$2_2") (pintype "passive"))
      (node (ref "C19") (pin "2") (pinfunction "P$2_2") (pintype "passive"))
      (node (ref "C2") (pin "2") (pinfunction "P$2_2") (pintype "passive"))
      (node (ref "C20") (pin "2") (pinfunction "P$2_2") (pintype "passive"))
      (node (ref "C21") (pin "2") (pinfunction "P$2_2") (pintype "passive"))
      (node (ref "C22") (pin "2") (pinfunction "P$2_2") (pintype "passive"))
      (node (ref "C23") (pin "2") (pinfunction "2_2") (pintype "passive"))
      (node (ref "C24") (pin "2") (pinfunction "P$2_2") (pintype "passive"))
      (node (ref "C25") (pin "2") (pinfunction "P$2_2") (pintype "passive"))
      (node (ref "C26") (pin "2") (pinfunction "P$2_2") (pintype "passive"))
      (node (ref "C27") (pin "2") (pinfunction "P$2_2") (pintype "passive"))
      (node (ref "C28") (pin "2") (pinfunction "P$2_2") (pintype "passive"))
      (node (ref "C29") (pin "2") (pinfunction "P$2_2") (pintype "passive"))
      (node (ref "C3") (pin "2") (pinfunction "P$2_2") (pintype "passive"))
      (node (ref "C30") (pin "2") (pinfunction "P$2_2") (pintype "passive"))
      (node (ref "C31") (pin "2") (pinfunction "P$2_2") (pintype "passive"))
      (node (ref "C4") (pin "2") (pinfunction "P$2_2") (pintype "passive"))
      (node (ref "C5") (pin "-") (pinfunction "-_-") (pintype "passive"))
      (node (ref "C6") (pin "-") (pinfunction "-_-") (pintype "passive"))
      (node (ref "C8") (pin "1") (pinfunction "P$1_1") (pintype "passive"))
      (node (ref "C9") (pin "2") (pinfunction "P$2_2") (pintype "passive"))
      (node (ref "CN2") (pin "GND") (pinfunction "GND_GND") (pintype "power_in"))
      (node (ref "IC1") (pin "11") (pinfunction "GND_11") (pintype "power_in"))
      (node (ref "IC1") (pin "32") (pinfunction "GND1_32") (pintype "power_in"))
      (node (ref "IC1") (pin "62") (pinfunction "GND2_62") (pintype "power_in"))
      (node (ref "IC1") (pin "81") (pinfunction "GND3_81") (pintype "power_in"))
      (node (ref "IC1") (pin "99") (pinfunction "AGND_99") (pintype "power_in"))
      (node (ref "IC2") (pin "11") (pinfunction "I_11") (pintype "input"))
      (node (ref "IC2") (pin "14") (pinfunction "I_14") (pintype "input"))
      (node (ref "IC2") (pin "8") (pinfunction "VSS_8") (pintype "power_in"))
      (node (ref "IC3") (pin "3") (pinfunction "GND_3") (pintype "passive"))
      (node (ref "IC4") (pin "2") (pinfunction "GND_2") (pintype "bidirectional"))
      (node (ref "IC5") (pin "3") (pinfunction "GND_3") (pintype "passive"))
      (node (ref "ICSP") (pin "6") (pinfunction "6_6") (pintype "bidirectional"))
      (node (ref "LED1") (pin "C") (pinfunction "C_C") (pintype "passive"))
      (node (ref "LED2") (pin "C") (pinfunction "C_C") (pintype "passive"))
      (node (ref "LEFT_HEADERS") (pin "7") (pinfunction "7_7") (pintype "passive"))
      (node (ref "R11") (pin "2") (pinfunction "2_2") (pintype "passive"))
      (node (ref "RIGHT_HEADERS") (pin "9") (pinfunction "9_9") (pintype "passive"))
      (node (ref "S1") (pin "1") (pinfunction "1_1") (pintype "passive"))
      (node (ref "S1") (pin "2") (pinfunction "2_2") (pintype "passive"))
      (node (ref "TOP_HEADER") (pin "2") (pinfunction "2_2") (pintype "passive"))
      (node (ref "U$15") (pin "10") (pinfunction "GND_10") (pintype "power_in"))
      (node (ref "U$55") (pin "P$1") (pinfunction "GND_P$1") (pintype "bidirectional"))
      (node (ref "U$55") (pin "P$2") (pinfunction "GND_P$2") (pintype "bidirectional"))
      (node (ref "U1") (pin "18") (pinfunction "GND2_18") (pintype "power_in"))
      (node (ref "U1") (pin "21") (pinfunction "GND3_21") (pintype "power_in"))
      (node (ref "U1") (pin "25") (pinfunction "AGND_25") (pintype "power_in"))
      (node (ref "U1") (pin "7") (pinfunction "GND1_7") (pintype "power_in"))
      (node (ref "U10") (pin "3") (pinfunction "VSS_3") (pintype "power_in"))
      (node (ref "U10") (pin "8") (pinfunction "VSS_8") (pintype "power_in"))
      (node (ref "U10") (pin "9") (pinfunction "VSS_9") (pintype "power_in"))
      (node (ref "U11") (pin "2") (pinfunction "GND_2") (pintype "power_in"))
      (node (ref "U2") (pin "1") (pinfunction "RSVRD(GND)_1") (pintype "bidirectional"))
      (node (ref "U2") (pin "3") (pinfunction "RSVRD(GND)_3") (pintype "bidirectional"))
      (node (ref "U2") (pin "6") (pinfunction "GND_6") (pintype "power_in"))
      (node (ref "U2") (pin "7") (pinfunction "GND_7") (pintype "power_in"))
      (node (ref "U3") (pin "2") (pinfunction "GND_2") (pintype "power_in"))
      (node (ref "U4") (pin "P$12") (pinfunction "GND_P$12") (pintype "bidirectional"))
      (node (ref "U4") (pin "P$19") (pinfunction "GND_P$19") (pintype "bidirectional"))
      (node (ref "U4") (pin "P$3") (pinfunction "GND_P$3") (pintype "bidirectional"))
      (node (ref "U4") (pin "P$8") (pinfunction "GND_P$8") (pintype "bidirectional"))
      (node (ref "U5") (pin "2") (pinfunction "GND_2") (pintype "power_in"))
      (node (ref "U6") (pin "3") (pinfunction "VSS_3") (pintype "power_in"))
      (node (ref "U6") (pin "8") (pinfunction "VSS_8") (pintype "power_in"))
      (node (ref "U6") (pin "9") (pinfunction "VSS_9") (pintype "power_in"))
      (node (ref "U7") (pin "3") (pinfunction "VSS_3") (pintype "power_in"))
      (node (ref "U7") (pin "8") (pinfunction "VSS_8") (pintype "power_in"))
      (node (ref "U7") (pin "9") (pinfunction "VSS_9") (pintype "power_in"))
      (node (ref "U8") (pin "2") (pinfunction "GND_2") (pintype "power_in"))
      (node (ref "U9") (pin "2") (pinfunction "GND_2") (pintype "power_in"))
      (node (ref "X1") (pin "6") (pinfunction "VSS_6") (pintype "power_in"))
      (node (ref "X1") (pin "MT1") (pinfunction "GND_MT1") (pintype "power_in"))
      (node (ref "X1") (pin "MT2") (pinfunction "GND1_MT2") (pintype "power_in"))
    )
    (net (code "87") (name "Net-(ACT-PadC)") (class "Default")
      (node (ref "ACT") (pin "C") (pinfunction "C_C") (pintype "passive"))
      (node (ref "R1") (pin "2") (pinfunction "2_2") (pintype "passive"))
    )
    (net (code "88") (name "Net-(B1-+-Pad+$1)") (class "Default")
      (node (ref "B1") (pin "+$1") (pinfunction "+_+$1") (pintype "passive"))
      (node (ref "B1") (pin "+$2") (pinfunction "+_+$2") (pintype "passive"))
      (node (ref "D4") (pin "A") (pinfunction "A_A") (pintype "passive"))
    )
    (net (code "89") (name "Net-(C7-P$1)") (class "Default")
      (node (ref "C7") (pin "1") (pinfunction "P$1_1") (pintype "passive"))
      (node (ref "U1") (pin "2") (pinfunction "DTR_2") (pintype "bidirectional"))
    )
    (net (code "90") (name "Net-(C18-P$1)") (class "Default")
      (node (ref "C18") (pin "1") (pinfunction "P$1_1") (pintype "passive"))
      (node (ref "U2") (pin "14") (pinfunction "VCC_14") (pintype "power_in"))
      (node (ref "U2") (pin "15") (pinfunction "VCC_15") (pintype "power_in"))
      (node (ref "U3") (pin "5") (pinfunction "OUT_5") (pintype "power_in"))
    )
    (net (code "91") (name "Net-(C20-P$1)") (class "Default")
      (node (ref "C20") (pin "1") (pinfunction "P$1_1") (pintype "passive"))
      (node (ref "C22") (pin "1") (pinfunction "P$1_1") (pintype "passive"))
      (node (ref "FB1") (pin "2") (pinfunction "P$2_2") (pintype "bidirectional"))
      (node (ref "R2") (pin "2") (pinfunction "2_2") (pintype "passive"))
      (node (ref "U4") (pin "P$1") (pinfunction "VCC_P$1") (pintype "bidirectional"))
    )
    (net (code "92") (name "Net-(C21-P$1)") (class "Default")
      (node (ref "C21") (pin "1") (pinfunction "P$1_1") (pintype "passive"))
      (node (ref "R10") (pin "1") (pinfunction "1_1") (pintype "passive"))
      (node (ref "U5") (pin "3") (pinfunction "EN_3") (pintype "input"))
    )
    (net (code "93") (name "Net-(FB1-P$1)") (class "Default")
      (node (ref "FB1") (pin "1") (pinfunction "P$1_1") (pintype "bidirectional"))
      (node (ref "U5") (pin "5") (pinfunction "OUT_5") (pintype "power_in"))
    )
    (net (code "94") (name "Net-(IC2A-O)") (class "Default")
      (node (ref "IC2") (pin "2") (pinfunction "O_2") (pintype "output"))
      (node (ref "X1") (pin "5") (pinfunction "SCLK_5") (pintype "input"))
    )
    (net (code "95") (name "Net-(IC2B-O)") (class "Default")
      (node (ref "IC2") (pin "4") (pinfunction "O_4") (pintype "output"))
      (node (ref "X1") (pin "3") (pinfunction "DATA_IN_3") (pintype "input"))
    )
    (net (code "96") (name "Net-(IC2C-O)") (class "Default")
      (node (ref "IC2") (pin "6") (pinfunction "O_6") (pintype "output"))
      (node (ref "R1") (pin "1") (pinfunction "1_1") (pintype "passive"))
      (node (ref "X1") (pin "2") (pinfunction "CS_2") (pintype "input"))
    )
    (net (code "97") (name "Net-(IC2D-O)") (class "Default")
      (node (ref "ACT") (pin "A") (pinfunction "A_A") (pintype "passive"))
      (node (ref "IC2") (pin "10") (pinfunction "O_10") (pintype "output"))
    )
    (net (code "98") (name "Net-(IC5-VI)") (class "Default")
      (node (ref "D5") (pin "C") (pinfunction "C_C") (pintype "passive"))
      (node (ref "IC5") (pin "1") (pinfunction "VI_1") (pintype "input"))
    )
    (net (code "99") (name "Net-(IC5-VO)") (class "Default")
      (node (ref "IC5") (pin "2") (pinfunction "VO_2") (pintype "passive"))
      (node (ref "U$15") (pin "1") (pinfunction "VCC_1") (pintype "power_in"))
    )
    (net (code "100") (name "Net-(LED1-PadA)") (class "Default")
      (node (ref "LED1") (pin "A") (pinfunction "A_A") (pintype "passive"))
      (node (ref "R4") (pin "1") (pinfunction "1_1") (pintype "passive"))
    )
    (net (code "101") (name "Net-(LED2-PadA)") (class "Default")
      (node (ref "LED2") (pin "A") (pinfunction "A_A") (pintype "passive"))
      (node (ref "R5") (pin "1") (pinfunction "1_1") (pintype "passive"))
    )
    (net (code "102") (name "Net-(LED3-PadC)") (class "Default")
      (node (ref "LED3") (pin "C") (pinfunction "C_C") (pintype "passive"))
      (node (ref "R8") (pin "1") (pinfunction "1_1") (pintype "passive"))
    )
    (net (code "103") (name "Net-(LED4-PadC)") (class "Default")
      (node (ref "LED4") (pin "C") (pinfunction "C_C") (pintype "passive"))
      (node (ref "R9") (pin "1") (pinfunction "1_1") (pintype "passive"))
    )
    (net (code "104") (name "Net-(LED5-PadC)") (class "Default")
      (node (ref "LED5") (pin "C") (pinfunction "C_C") (pintype "passive"))
      (node (ref "R11") (pin "1") (pinfunction "1_1") (pintype "passive"))
    )
    (net (code "105") (name "Net-(SG1-2)") (class "Default")
      (node (ref "100") (pin "1") (pinfunction "1_1") (pintype "passive"))
      (node (ref "SG1") (pin "-") (pinfunction "2_-") (pintype "passive"))
    )
    (net (code "106") (name "Net-(U$55-SIGNAL)") (class "Default")
      (node (ref "U$55") (pin "P$3") (pinfunction "SIGNAL_P$3") (pintype "bidirectional"))
      (node (ref "U4") (pin "P$11") (pinfunction "EX_ANT_P$11") (pintype "bidirectional"))
    )
    (net (code "107") (name "Net-(U1-RXLED)") (class "Default")
      (node (ref "R9") (pin "2") (pinfunction "2_2") (pintype "passive"))
      (node (ref "U1") (pin "22") (pinfunction "RXLED_22") (pintype "bidirectional"))
    )
    (net (code "108") (name "Net-(U1-TXLED)") (class "Default")
      (node (ref "R8") (pin "2") (pinfunction "2_2") (pintype "passive"))
      (node (ref "U1") (pin "23") (pinfunction "TXLED_23") (pintype "bidirectional"))
    )
    (net (code "109") (name "Net-(U1-USB+)") (class "Default")
      (node (ref "CN2") (pin "D+") (pinfunction "D+_D+") (pintype "bidirectional"))
      (node (ref "U1") (pin "15") (pinfunction "USB+_15") (pintype "bidirectional"))
    )
    (net (code "110") (name "Net-(U1-USB-)") (class "Default")
      (node (ref "CN2") (pin "D-") (pinfunction "D-_D-") (pintype "bidirectional"))
      (node (ref "U1") (pin "16") (pinfunction "USB-_16") (pintype "bidirectional"))
    )
    (net (code "111") (name "Net-(U4-RX)") (class "Default")
      (node (ref "D3") (pin "A") (pinfunction "A_A") (pintype "passive"))
      (node (ref "R2") (pin "1") (pinfunction "1_1") (pintype "passive"))
      (node (ref "U4") (pin "P$10") (pinfunction "RX_P$10") (pintype "bidirectional"))
    )
    (net (code "112") (name "RESET") (class "Default")
      (node (ref "BOTTOM_HEADER") (pin "1") (pinfunction "1_1") (pintype "passive"))
      (node (ref "C4") (pin "1") (pinfunction "P$1_1") (pintype "passive"))
      (node (ref "C7") (pin "2") (pinfunction "P$2_2") (pintype "passive"))
      (node (ref "IC1") (pin "30") (pinfunction "RESET_30") (pintype "input"))
      (node (ref "ICSP") (pin "5") (pinfunction "5_5") (pintype "bidirectional"))
      (node (ref "R3") (pin "1") (pinfunction "1_1") (pintype "passive"))
      (node (ref "S1") (pin "3") (pinfunction "3_3") (pintype "passive"))
      (node (ref "S1") (pin "4") (pinfunction "4_4") (pintype "passive"))
    )
    (net (code "113") (name "VIN") (class "Default")
      (node (ref "C5") (pin "+") (pinfunction "+_+") (pintype "passive"))
      (node (ref "D1") (pin "C") (pinfunction "C_C") (pintype "passive"))
      (node (ref "IC3") (pin "1") (pinfunction "VI_1") (pintype "input"))
    )
    (net (code "114") (name "VUSB") (class "Default")
      (node (ref "C10") (pin "2") (pinfunction "P$2_2") (pintype "passive"))
      (node (ref "C23") (pin "1") (pinfunction "1_1") (pintype "passive"))
      (node (ref "CN2") (pin "VBUS") (pinfunction "VBUS_VBUS") (pintype "power_in"))
      (node (ref "D2") (pin "A") (pinfunction "A_A") (pintype "passive"))
    )
    (net (code "115") (name "unconnected-(CN2-PadID)") (class "Default")
      (node (ref "CN2") (pin "ID") (pinfunction "ID_ID") (pintype "bidirectional"))
    )
    (net (code "116") (name "unconnected-(IC1-(CLKO{slash}ICP3{slash}INT7)PE7-Pad9)") (class "Default")
      (node (ref "IC1") (pin "9") (pinfunction "(CLKO/ICP3/INT7)PE7_9") (pintype "bidirectional"))
    )
    (net (code "117") (name "unconnected-(IC1-(ICP1)PD4-Pad47)") (class "Default")
      (node (ref "IC1") (pin "47") (pinfunction "(ICP1)PD4_47") (pintype "bidirectional"))
    )
    (net (code "118") (name "unconnected-(IC1-(T1)PD6-Pad49)") (class "Default")
      (node (ref "IC1") (pin "49") (pinfunction "(T1)PD6_49") (pintype "bidirectional"))
    )
    (net (code "119") (name "unconnected-(IC1-(T3{slash}INT6)PE6-Pad8)") (class "Default")
      (node (ref "IC1") (pin "8") (pinfunction "(T3/INT6)PE6_8") (pintype "bidirectional"))
    )
    (net (code "120") (name "unconnected-(IC1-(TOSC1)PG4-Pad29)") (class "Default")
      (node (ref "IC1") (pin "29") (pinfunction "(TOSC1)PG4_29") (pintype "bidirectional"))
    )
    (net (code "121") (name "unconnected-(IC1-(TOSC2)PG3-Pad28)") (class "Default")
      (node (ref "IC1") (pin "28") (pinfunction "(TOSC2)PG3_28") (pintype "bidirectional"))
    )
    (net (code "122") (name "unconnected-(IC1-(XCK0{slash}AIN0)PE2-Pad4)") (class "Default")
      (node (ref "IC1") (pin "4") (pinfunction "(XCK0/AIN0)PE2_4") (pintype "bidirectional"))
    )
    (net (code "123") (name "unconnected-(IC1-(XCK1)PD5-Pad48)") (class "Default")
      (node (ref "IC1") (pin "48") (pinfunction "(XCK1)PD5_48") (pintype "bidirectional"))
    )
    (net (code "124") (name "unconnected-(IC1-PH2(XCK2)-Pad14)") (class "Default")
      (node (ref "IC1") (pin "14") (pinfunction "PH2(XCK2)_14") (pintype "bidirectional"))
    )
    (net (code "125") (name "unconnected-(IC1-PH7(T4)-Pad27)") (class "Default")
      (node (ref "IC1") (pin "27") (pinfunction "PH7(T4)_27") (pintype "bidirectional"))
    )
    (net (code "126") (name "unconnected-(IC1-PJ2(XCK3{slash}PCINT11)-Pad65)") (class "Default")
      (node (ref "IC1") (pin "65") (pinfunction "PJ2(XCK3/PCINT11)_65") (pintype "bidirectional"))
    )
    (net (code "127") (name "unconnected-(IC1-PJ3(PCINT12)-Pad66)") (class "Default")
      (node (ref "IC1") (pin "66") (pinfunction "PJ3(PCINT12)_66") (pintype "bidirectional"))
    )
    (net (code "128") (name "unconnected-(IC1-PJ4(PCINT13)-Pad67)") (class "Default")
      (node (ref "IC1") (pin "67") (pinfunction "PJ4(PCINT13)_67") (pintype "bidirectional"))
    )
    (net (code "129") (name "unconnected-(IC1-PJ5(PCINT14)-Pad68)") (class "Default")
      (node (ref "IC1") (pin "68") (pinfunction "PJ5(PCINT14)_68") (pintype "bidirectional"))
    )
    (net (code "130") (name "unconnected-(IC1-PJ6(PCINT15)-Pad69)") (class "Default")
      (node (ref "IC1") (pin "69") (pinfunction "PJ6(PCINT15)_69") (pintype "bidirectional"))
    )
    (net (code "131") (name "unconnected-(IC1-PJ7-Pad79)") (class "Default")
      (node (ref "IC1") (pin "79") (pinfunction "PJ7_79") (pintype "bidirectional"))
    )
    (net (code "132") (name "unconnected-(IC2E-O-Pad12)") (class "Default")
      (node (ref "IC2") (pin "12") (pinfunction "O_12") (pintype "output"))
    )
    (net (code "133") (name "unconnected-(IC2F-O-Pad15)") (class "Default")
      (node (ref "IC2") (pin "15") (pinfunction "O_15") (pintype "output"))
    )
    (net (code "134") (name "unconnected-(IC4-BYP-Pad4)") (class "Default")
      (node (ref "IC4") (pin "4") (pinfunction "BYP_4") (pintype "bidirectional"))
    )
    (net (code "135") (name "unconnected-(U$15-AD0{slash}DIO0-Pad20)") (class "Default")
      (node (ref "U$15") (pin "20") (pinfunction "AD0/DIO0_20") (pintype "bidirectional"))
    )
    (net (code "136") (name "unconnected-(U$15-AD1{slash}DIO1-Pad19)") (class "Default")
      (node (ref "U$15") (pin "19") (pinfunction "AD1/DIO1_19") (pintype "bidirectional"))
    )
    (net (code "137") (name "unconnected-(U$15-AD2{slash}DIO2-Pad18)") (class "Default")
      (node (ref "U$15") (pin "18") (pinfunction "AD2/DIO2_18") (pintype "bidirectional"))
    )
    (net (code "138") (name "unconnected-(U$15-AD3{slash}DIO3-Pad17)") (class "Default")
      (node (ref "U$15") (pin "17") (pinfunction "AD3/DIO3_17") (pintype "bidirectional"))
    )
    (net (code "139") (name "unconnected-(U$15-AD4{slash}DIO4-Pad11)") (class "Default")
      (node (ref "U$15") (pin "11") (pinfunction "AD4/DIO4_11") (pintype "bidirectional"))
    )
    (net (code "140") (name "unconnected-(U$15-ASC{slash}AD5{slash}DIO5-Pad15)") (class "Default")
      (node (ref "U$15") (pin "15") (pinfunction "ASC/AD5/DIO5_15") (pintype "bidirectional"))
    )
    (net (code "141") (name "unconnected-(U$15-CTS{slash}DIO7-Pad12)") (class "Default")
      (node (ref "U$15") (pin "12") (pinfunction "CTS/DIO7_12") (pintype "bidirectional"))
    )
    (net (code "142") (name "unconnected-(U$15-DO8-Pad4)") (class "Default")
      (node (ref "U$15") (pin "4") (pinfunction "DO8_4") (pintype "output"))
    )
    (net (code "143") (name "unconnected-(U$15-DTR{slash}DI8-Pad9)") (class "Default")
      (node (ref "U$15") (pin "9") (pinfunction "DTR/DI8_9") (pintype "input"))
    )
    (net (code "144") (name "unconnected-(U$15-ON{slash}SLEEP-Pad13)") (class "Default")
      (node (ref "U$15") (pin "13") (pinfunction "ON/SLEEP_13") (pintype "output"))
    )
    (net (code "145") (name "unconnected-(U$15-PWM0{slash}RSSI-Pad6)") (class "Default")
      (node (ref "U$15") (pin "6") (pinfunction "PWM0/RSSI_6") (pintype "output"))
    )
    (net (code "146") (name "unconnected-(U$15-PWM1-Pad7)") (class "Default")
      (node (ref "U$15") (pin "7") (pinfunction "PWM1_7") (pintype "output"))
    )
    (net (code "147") (name "unconnected-(U$15-RESERVED-Pad8)") (class "Default")
      (node (ref "U$15") (pin "8") (pinfunction "RESERVED_8") (pintype "no_connect"))
    )
    (net (code "148") (name "unconnected-(U$15-RESET-Pad5)") (class "Default")
      (node (ref "U$15") (pin "5") (pinfunction "RESET_5") (pintype "input"))
    )
    (net (code "149") (name "unconnected-(U$15-RTS{slash}AD6{slash}DIO6-Pad16)") (class "Default")
      (node (ref "U$15") (pin "16") (pinfunction "RTS/AD6/DIO6_16") (pintype "bidirectional"))
    )
    (net (code "150") (name "unconnected-(U$15-VREF-Pad14)") (class "Default")
      (node (ref "U$15") (pin "14") (pinfunction "VREF_14") (pintype "input"))
    )
    (net (code "151") (name "unconnected-(U1-CTS-Pad11)") (class "Default")
      (node (ref "U1") (pin "11") (pinfunction "CTS_11") (pintype "bidirectional"))
    )
    (net (code "152") (name "unconnected-(U1-RTS-Pad3)") (class "Default")
      (node (ref "U1") (pin "3") (pinfunction "RTS_3") (pintype "bidirectional"))
    )
    (net (code "153") (name "unconnected-(U1-TEST-Pad26)") (class "Default")
      (node (ref "U1") (pin "26") (pinfunction "TEST_26") (pintype "input"))
    )
    (net (code "154") (name "unconnected-(U2-NC-Pad8)") (class "Default")
      (node (ref "U2") (pin "8") (pinfunction "NC_8") (pintype "no_connect"))
    )
    (net (code "155") (name "unconnected-(U2-NC-Pad9)") (class "Default")
      (node (ref "U2") (pin "9") (pinfunction "NC_9") (pintype "no_connect"))
    )
    (net (code "156") (name "unconnected-(U2-NC-Pad10)") (class "Default")
      (node (ref "U2") (pin "10") (pinfunction "NC_10") (pintype "no_connect"))
    )
    (net (code "157") (name "unconnected-(U2-NC-Pad11)") (class "Default")
      (node (ref "U2") (pin "11") (pinfunction "NC_11") (pintype "no_connect"))
    )
    (net (code "158") (name "unconnected-(U2-NC-Pad12)") (class "Default")
      (node (ref "U2") (pin "12") (pinfunction "NC_12") (pintype "no_connect"))
    )
    (net (code "159") (name "unconnected-(U2-NC-Pad13)") (class "Default")
      (node (ref "U2") (pin "13") (pinfunction "NC_13") (pintype "no_connect"))
    )
    (net (code "160") (name "unconnected-(U3-P4-Pad4)") (class "Default")
      (node (ref "U3") (pin "4") (pinfunction "P4_4") (pintype "bidirectional"))
    )
    (net (code "161") (name "unconnected-(U4-NC-PadP$6)") (class "Default")
      (node (ref "U4") (pin "P$6") (pinfunction "NC_P$6") (pintype "bidirectional"))
    )
    (net (code "162") (name "unconnected-(U4-NC-PadP$7)") (class "Default")
      (node (ref "U4") (pin "P$7") (pinfunction "NC_P$7") (pintype "bidirectional"))
    )
    (net (code "163") (name "unconnected-(U4-NC-PadP$15)") (class "Default")
      (node (ref "U4") (pin "P$15") (pinfunction "NC_P$15") (pintype "bidirectional"))
    )
    (net (code "164") (name "unconnected-(U4-NC-PadP$16)") (class "Default")
      (node (ref "U4") (pin "P$16") (pinfunction "NC_P$16") (pintype "bidirectional"))
    )
    (net (code "165") (name "unconnected-(U4-NC-PadP$17)") (class "Default")
      (node (ref "U4") (pin "P$17") (pinfunction "NC_P$17") (pintype "bidirectional"))
    )
    (net (code "166") (name "unconnected-(U4-NC-PadP$18)") (class "Default")
      (node (ref "U4") (pin "P$18") (pinfunction "NC_P$18") (pintype "bidirectional"))
    )
    (net (code "167") (name "unconnected-(U4-NC-PadP$20)") (class "Default")
      (node (ref "U4") (pin "P$20") (pinfunction "NC_P$20") (pintype "bidirectional"))
    )
    (net (code "168") (name "unconnected-(U4-NRESET-PadP$2)") (class "Default")
      (node (ref "U4") (pin "P$2") (pinfunction "NRESET_P$2") (pintype "bidirectional"))
    )
    (net (code "169") (name "unconnected-(U4-RTCM-PadP$14)") (class "Default")
      (node (ref "U4") (pin "P$14") (pinfunction "RTCM_P$14") (pintype "bidirectional"))
    )
    (net (code "170") (name "unconnected-(U5-P4-Pad4)") (class "Default")
      (node (ref "U5") (pin "4") (pinfunction "P4_4") (pintype "bidirectional"))
    )
    (net (code "171") (name "unconnected-(U6-INT-Pad7)") (class "Default")
      (node (ref "U6") (pin "7") (pinfunction "INT_7") (pintype "output"))
    )
    (net (code "172") (name "unconnected-(U7-INT-Pad7)") (class "Default")
      (node (ref "U7") (pin "7") (pinfunction "INT_7") (pintype "output"))
    )
    (net (code "173") (name "unconnected-(U8-P4-Pad4)") (class "Default")
      (node (ref "U8") (pin "4") (pinfunction "P4_4") (pintype "bidirectional"))
    )
    (net (code "174") (name "unconnected-(U9-P4-Pad4)") (class "Default")
      (node (ref "U9") (pin "4") (pinfunction "P4_4") (pintype "bidirectional"))
    )
    (net (code "175") (name "unconnected-(U10-INT-Pad7)") (class "Default")
      (node (ref "U10") (pin "7") (pinfunction "INT_7") (pintype "output"))
    )
    (net (code "176") (name "unconnected-(U11-P4-Pad4)") (class "Default")
      (node (ref "U11") (pin "4") (pinfunction "P4_4") (pintype "bidirectional"))
    )
    (net (code "177") (name "unconnected-(X1-CARD_DETECT1-PadCD2)") (class "Default")
      (node (ref "X1") (pin "CD2") (pinfunction "CARD_DETECT1_CD2") (pintype "passive"))
    )
    (net (code "178") (name "unconnected-(X1-DAT1-Pad8)") (class "Default")
      (node (ref "X1") (pin "8") (pinfunction "DAT1_8") (pintype "bidirectional"))
    )
    (net (code "179") (name "unconnected-(X1-DAT2-Pad1)") (class "Default")
      (node (ref "X1") (pin "1") (pinfunction "DAT2_1") (pintype "bidirectional"))
    )
  )
)
